# Card_Edge_Connector.net
KiCad netlist of a schematic drawn in Altium Designer
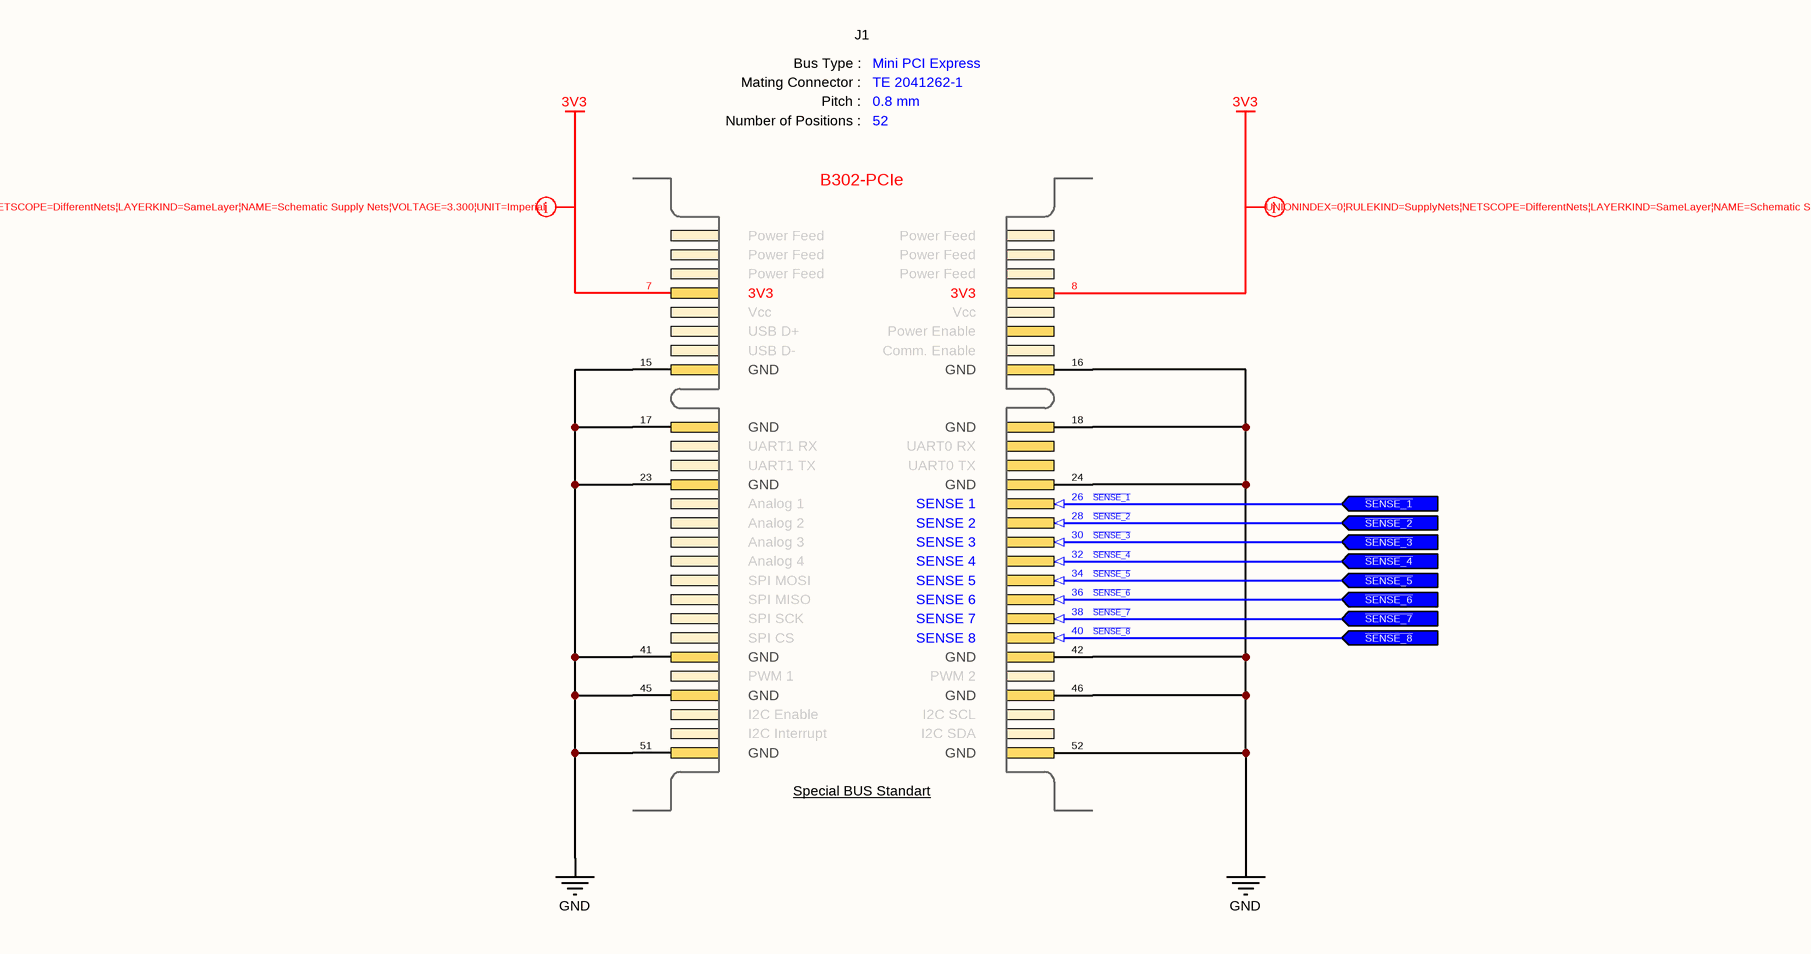
[diagram p0: Card Edge Connector.SchDoc]

(export (version "E")
  (design (tool "Eeschema 10.0.6"))
  (components
    (comp (ref "J1")
      (value "Connector - Mini PCI-E (Male B302-PCIe)")
      (footprint "PCB - Mini PCI Express")
      (description "Mini PCI-Express gold finger connector.")
      (fields
        (field (name "BUS TYPE") "Mini PCI Express")
        (field (name "MATING CONNECTOR") "TE 2041262-1")
        (field (name "PITCH") "0.8 mm")
        (field (name "NUMBER OF POSITIONS") "52")
      )
      (libsource (lib "Akkoyun") (part "Connector - Mini PCI-E (Male B302-PCIe)"))
    )
  )
  (nets
    (net (code "1") (name "/~{SENSE_1}") (class "Default")
      (node (ref "J1") (pin "26") (pinfunction "Pin-26_26") (pintype "input"))
    )
    (net (code "2") (name "/~{SENSE_2}") (class "Default")
      (node (ref "J1") (pin "28") (pinfunction "Pin-28_28") (pintype "input"))
    )
    (net (code "3") (name "/~{SENSE_3}") (class "Default")
      (node (ref "J1") (pin "30") (pinfunction "Pin-30_30") (pintype "input"))
    )
    (net (code "4") (name "/~{SENSE_4}") (class "Default")
      (node (ref "J1") (pin "32") (pinfunction "Pin-32_32") (pintype "input"))
    )
    (net (code "5") (name "/~{SENSE_5}") (class "Default")
      (node (ref "J1") (pin "34") (pinfunction "Pin-34_34") (pintype "input"))
    )
    (net (code "6") (name "/~{SENSE_6}") (class "Default")
      (node (ref "J1") (pin "36") (pinfunction "Pin-36_36") (pintype "input"))
    )
    (net (code "7") (name "/~{SENSE_7}") (class "Default")
      (node (ref "J1") (pin "38") (pinfunction "Pin-38_38") (pintype "input"))
    )
    (net (code "8") (name "/~{SENSE_8}") (class "Default")
      (node (ref "J1") (pin "40") (pinfunction "Pin-40_40") (pintype "input"))
    )
    (net (code "9") (name "3V3") (class "Default")
      (node (ref "J1") (pin "7") (pinfunction "Pin-7_7") (pintype "power_in"))
      (node (ref "J1") (pin "8") (pinfunction "Pin-8_8") (pintype "power_in"))
    )
    (net (code "10") (name "GND") (class "Default")
      (node (ref "J1") (pin "15") (pinfunction "Pin-15_15") (pintype "power_in"))
      (node (ref "J1") (pin "16") (pinfunction "Pin-16_16") (pintype "power_in"))
      (node (ref "J1") (pin "17") (pinfunction "Pin-17_17") (pintype "power_in"))
      (node (ref "J1") (pin "18") (pinfunction "Pin-18_18") (pintype "power_in"))
      (node (ref "J1") (pin "23") (pinfunction "Pin-23_23") (pintype "power_in"))
      (node (ref "J1") (pin "24") (pinfunction "Pin-24_24") (pintype "power_in"))
      (node (ref "J1") (pin "41") (pinfunction "Pin-41_41") (pintype "power_in"))
      (node (ref "J1") (pin "42") (pinfunction "Pin-42_42") (pintype "power_in"))
      (node (ref "J1") (pin "45") (pinfunction "Pin-45_45") (pintype "power_in"))
      (node (ref "J1") (pin "46") (pinfunction "Pin-46_46") (pintype "power_in"))
      (node (ref "J1") (pin "51") (pinfunction "Pin-51_51") (pintype "power_in"))
      (node (ref "J1") (pin "52") (pinfunction "Pin-52_52") (pintype "power_in"))
    )
  )
)
